# XR3.net
KiCad netlist of a schematic drawn in EAGLE
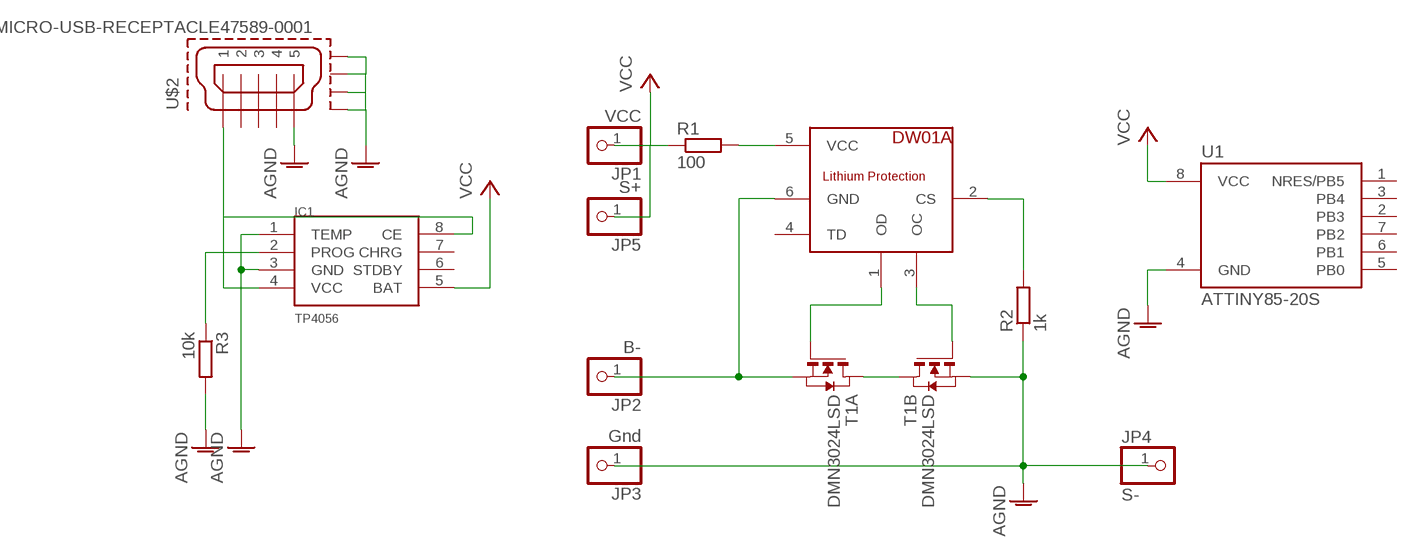
[diagram p0: schematic, sheet 1]

(export (version "E")
  (design (tool "Eeschema 10.0.6"))
  (components
    (comp (ref "IC1")
      (value "TP4056")
      (footprint "eagle-import:SOP-8")
      (libsource (lib "eagle-import") (part "TP4056"))
    )
    (comp (ref "JP1")
      (value "VCC")
      (footprint "eagle-import:1X01")
      (libsource (lib "eagle-import") (part "PINHD-1X1"))
    )
    (comp (ref "JP2")
      (value "B-")
      (footprint "eagle-import:1X01")
      (libsource (lib "eagle-import") (part "PINHD-1X1"))
    )
    (comp (ref "JP3")
      (value "Gnd")
      (footprint "eagle-import:1X01")
      (libsource (lib "eagle-import") (part "PINHD-1X1"))
    )
    (comp (ref "JP4")
      (value "S-")
      (footprint "eagle-import:1X01")
      (libsource (lib "eagle-import") (part "PINHD-1X1"))
    )
    (comp (ref "JP5")
      (value "S+")
      (footprint "eagle-import:1X01")
      (libsource (lib "eagle-import") (part "PINHD-1X1"))
    )
    (comp (ref "R1")
      (value "100")
      (footprint "eagle-import:R0603")
      (libsource (lib "eagle-import") (part "R-EU_R0603"))
    )
    (comp (ref "R2")
      (value "1k")
      (footprint "eagle-import:R0603")
      (libsource (lib "eagle-import") (part "R-EU_R0603"))
    )
    (comp (ref "R3")
      (value "10k")
      (footprint "eagle-import:R0603")
      (libsource (lib "eagle-import") (part "R-EU_R0603"))
    )
    (comp (ref "T1")
      (value "DMN3024LSD")
      (footprint "eagle-import:TSSOP-8")
      (libsource (lib "eagle-import") (part "DMN3024LSD"))
    )
    (comp (ref "U$1")
      (value "DW01A")
      (footprint "eagle-import:SOT23-6")
      (libsource (lib "eagle-import") (part "DW01A"))
    )
    (comp (ref "U$2")
      (value "MICRO-USB-RECEPTACLE47589-0001")
      (footprint "eagle-import:47589-0001")
      (libsource (lib "eagle-import") (part "MICRO-USB-RECEPTACLE47589-0001"))
    )
    (comp (ref "U1")
      (value "ATTINY85-20S")
      (footprint "eagle-import:SOIC8_EIAJ_208MIL")
      (libsource (lib "eagle-import") (part "ATTINY85S-20"))
    )
  )
  (nets
    (net (code "1") (name "AGND") (class "Default")
      (node (ref "IC1") (pin "1") (pinfunction "TEMP_1") (pintype "bidirectional"))
      (node (ref "IC1") (pin "3") (pinfunction "GND_3") (pintype "bidirectional"))
      (node (ref "JP3") (pin "1") (pinfunction "1_1") (pintype "passive"))
      (node (ref "JP4") (pin "1") (pinfunction "1_1") (pintype "passive"))
      (node (ref "R2") (pin "1") (pinfunction "1_1") (pintype "passive"))
      (node (ref "R3") (pin "2") (pinfunction "2_2") (pintype "passive"))
      (node (ref "T1") (pin "6") (pinfunction "S_6") (pintype "passive"))
      (node (ref "T1") (pin "7") (pinfunction "S_7") (pintype "passive"))
      (node (ref "U$2") (pin "5") (pinfunction "5_5") (pintype "input"))
      (node (ref "U$2") (pin "CASING1") (pinfunction "GND1_CASING1") (pintype "bidirectional"))
      (node (ref "U$2") (pin "CASING2") (pinfunction "GND2_CASING2") (pintype "bidirectional"))
      (node (ref "U$2") (pin "CASING3") (pinfunction "GND3_CASING3") (pintype "bidirectional"))
      (node (ref "U$2") (pin "CASING4") (pinfunction "GND4_CASING4") (pintype "bidirectional"))
      (node (ref "U1") (pin "4") (pinfunction "GND_4") (pintype "power_in"))
    )
    (net (code "2") (name "Net-(IC1-CE)") (class "Default")
      (node (ref "IC1") (pin "4") (pinfunction "VCC_4") (pintype "bidirectional"))
      (node (ref "IC1") (pin "8") (pinfunction "CE_8") (pintype "bidirectional"))
      (node (ref "U$2") (pin "1") (pinfunction "1_1") (pintype "input"))
    )
    (net (code "3") (name "Net-(IC1-PROG)") (class "Default")
      (node (ref "IC1") (pin "2") (pinfunction "PROG_2") (pintype "bidirectional"))
      (node (ref "R3") (pin "1") (pinfunction "1_1") (pintype "passive"))
    )
    (net (code "4") (name "Net-(T1A-D)") (class "Default")
      (node (ref "T1") (pin "1") (pinfunction "D_1") (pintype "passive"))
      (node (ref "T1") (pin "8") (pinfunction "D_8") (pintype "passive"))
    )
    (net (code "5") (name "Net-(T1A-G)") (class "Default")
      (node (ref "T1") (pin "4") (pinfunction "G_4") (pintype "passive"))
      (node (ref "U$1") (pin "1") (pinfunction "OD_1") (pintype "bidirectional"))
    )
    (net (code "6") (name "Net-(T1B-G)") (class "Default")
      (node (ref "T1") (pin "5") (pinfunction "G_5") (pintype "passive"))
      (node (ref "U$1") (pin "3") (pinfunction "OC_3") (pintype "bidirectional"))
    )
    (net (code "7") (name "Net-(U$1-CS)") (class "Default")
      (node (ref "R2") (pin "2") (pinfunction "2_2") (pintype "passive"))
      (node (ref "U$1") (pin "2") (pinfunction "CS_2") (pintype "bidirectional"))
    )
    (net (code "8") (name "Net-(U$1-GND)") (class "Default")
      (node (ref "JP2") (pin "1") (pinfunction "1_1") (pintype "passive"))
      (node (ref "T1") (pin "2") (pinfunction "S_2") (pintype "passive"))
      (node (ref "T1") (pin "3") (pinfunction "S_3") (pintype "passive"))
      (node (ref "U$1") (pin "6") (pinfunction "GND_6") (pintype "bidirectional"))
    )
    (net (code "9") (name "Net-(U$1-VCC)") (class "Default")
      (node (ref "R1") (pin "2") (pinfunction "2_2") (pintype "passive"))
      (node (ref "U$1") (pin "5") (pinfunction "VCC_5") (pintype "bidirectional"))
    )
    (net (code "10") (name "VCC") (class "Default")
      (node (ref "IC1") (pin "5") (pinfunction "BAT_5") (pintype "bidirectional"))
      (node (ref "JP1") (pin "1") (pinfunction "1_1") (pintype "passive"))
      (node (ref "JP5") (pin "1") (pinfunction "1_1") (pintype "passive"))
      (node (ref "R1") (pin "1") (pinfunction "1_1") (pintype "passive"))
      (node (ref "U1") (pin "8") (pinfunction "VCC_8") (pintype "power_in"))
    )
    (net (code "11") (name "unconnected-(IC1-CHRG-Pad7)") (class "Default")
      (node (ref "IC1") (pin "7") (pinfunction "CHRG_7") (pintype "bidirectional"))
    )
    (net (code "12") (name "unconnected-(IC1-STDBY-Pad6)") (class "Default")
      (node (ref "IC1") (pin "6") (pinfunction "STDBY_6") (pintype "bidirectional"))
    )
    (net (code "13") (name "unconnected-(U$1-TD-Pad4)") (class "Default")
      (node (ref "U$1") (pin "4") (pinfunction "TD_4") (pintype "bidirectional"))
    )
    (net (code "14") (name "unconnected-(U$2-Pad2)") (class "Default")
      (node (ref "U$2") (pin "2") (pinfunction "2_2") (pintype "input"))
    )
    (net (code "15") (name "unconnected-(U$2-Pad3)") (class "Default")
      (node (ref "U$2") (pin "3") (pinfunction "3_3") (pintype "input"))
    )
    (net (code "16") (name "unconnected-(U$2-Pad4)") (class "Default")
      (node (ref "U$2") (pin "4") (pinfunction "4_4") (pintype "input"))
    )
    (net (code "17") (name "unconnected-(U1-NRES{slash}PB5-Pad1)") (class "Default")
      (node (ref "U1") (pin "1") (pinfunction "NRES/PB5_1") (pintype "bidirectional"))
    )
    (net (code "18") (name "unconnected-(U1-PB0-Pad5)") (class "Default")
      (node (ref "U1") (pin "5") (pinfunction "PB0_5") (pintype "bidirectional"))
    )
    (net (code "19") (name "unconnected-(U1-PB1-Pad6)") (class "Default")
      (node (ref "U1") (pin "6") (pinfunction "PB1_6") (pintype "bidirectional"))
    )
    (net (code "20") (name "unconnected-(U1-PB2-Pad7)") (class "Default")
      (node (ref "U1") (pin "7") (pinfunction "PB2_7") (pintype "bidirectional"))
    )
    (net (code "21") (name "unconnected-(U1-PB3-Pad2)") (class "Default")
      (node (ref "U1") (pin "2") (pinfunction "PB3_2") (pintype "bidirectional"))
    )
    (net (code "22") (name "unconnected-(U1-PB4-Pad3)") (class "Default")
      (node (ref "U1") (pin "3") (pinfunction "PB4_3") (pintype "bidirectional"))
    )
  )
)
